# train_cont_R4.net
KiCad netlist of a schematic drawn in EAGLE
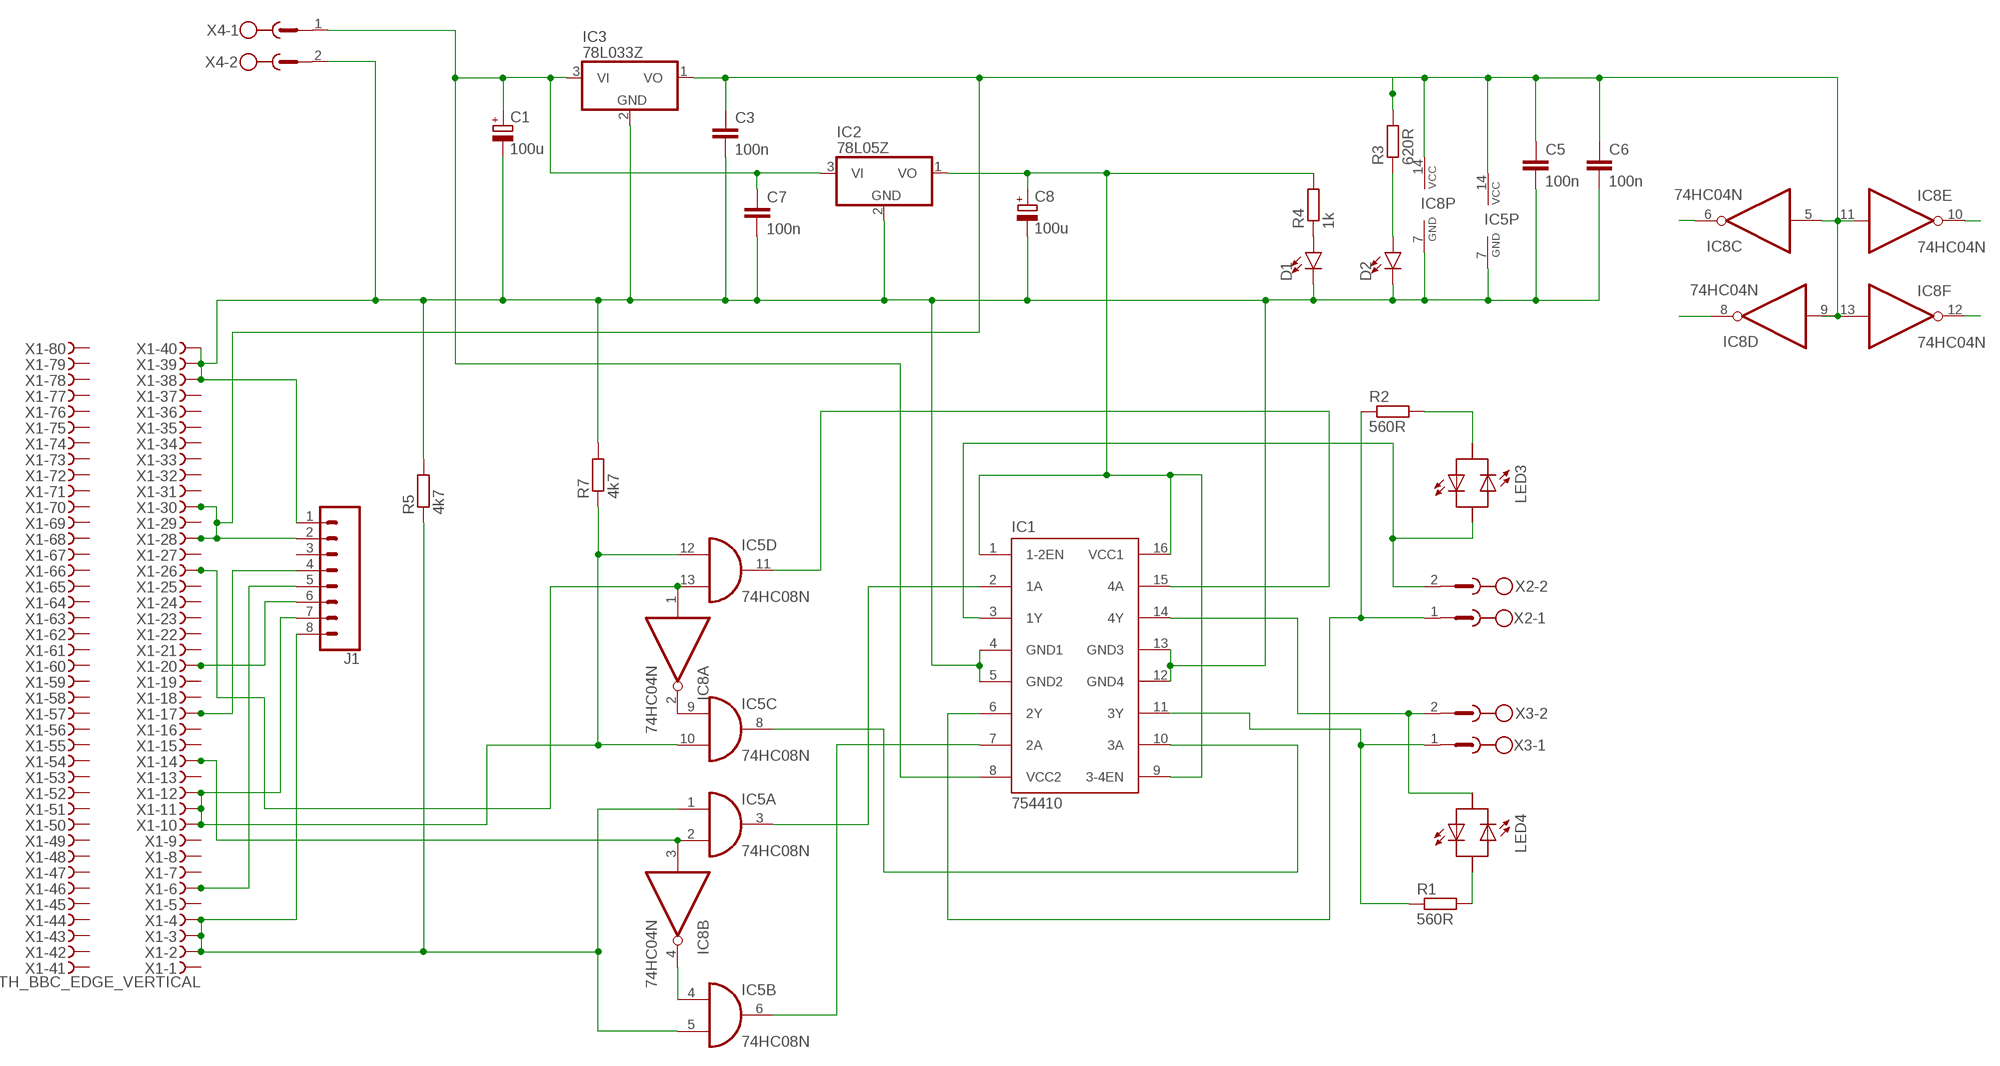
[diagram p0: schematic, sheet 1]

(export (version "E")
  (design (tool "Eeschema 10.0.6"))
  (components
    (comp (ref "C1")
      (value "100u")
      (footprint "eagle-import:E2,5-6E")
      (libsource (lib "eagle-import") (part "CPOL-EUE2,5-6E"))
    )
    (comp (ref "C3")
      (value "100n")
      (footprint "eagle-import:C050-025X075")
      (libsource (lib "eagle-import") (part "C-EU050-025X075"))
    )
    (comp (ref "C5")
      (value "100n")
      (footprint "eagle-import:C050-025X075")
      (libsource (lib "eagle-import") (part "C-EU050-025X075"))
    )
    (comp (ref "C6")
      (value "100n")
      (footprint "eagle-import:C050-025X075")
      (libsource (lib "eagle-import") (part "C-EU050-025X075"))
    )
    (comp (ref "C7")
      (value "100n")
      (footprint "eagle-import:C050-025X075")
      (libsource (lib "eagle-import") (part "C-EU050-025X075"))
    )
    (comp (ref "C8")
      (value "100u")
      (footprint "eagle-import:E2,5-6E")
      (libsource (lib "eagle-import") (part "CPOL-EUE2,5-6E"))
    )
    (comp (ref "D1")
      (value "LED3MM")
      (footprint "eagle-import:LED_3MM")
      (libsource (lib "eagle-import") (part "LED3MM"))
    )
    (comp (ref "D2")
      (value "LED3MM")
      (footprint "eagle-import:LED_3MM")
      (libsource (lib "eagle-import") (part "LED3MM"))
    )
    (comp (ref "IC1")
      (value "754410")
      (footprint "eagle-import:DIL16")
      (fields (field (name "MF") "Arrow Electronics") (field (name "MPN") "L293E"))
      (libsource (lib "eagle-import") (part "L293E"))
    )
    (comp (ref "IC2")
      (value "78L05Z")
      (footprint "eagle-import:TO92")
      (libsource (lib "eagle-import") (part "78ZL05"))
    )
    (comp (ref "IC3")
      (value "78L033Z")
      (footprint "eagle-import:TO92")
      (libsource (lib "eagle-import") (part "78ZL05"))
    )
    (comp (ref "IC5")
      (value "74HC08N")
      (footprint "eagle-import:DIL14")
      (libsource (lib "eagle-import") (part "7408NHC"))
    )
    (comp (ref "IC8")
      (value "74HC04N")
      (footprint "eagle-import:DIL14")
      (libsource (lib "eagle-import") (part "7404NAC"))
    )
    (comp (ref "J1")
      (value "CONN_08\"")
      (footprint "eagle-import:1X08")
      (libsource (lib "eagle-import") (part "CONN_08{dblquote}"))
    )
    (comp (ref "LED3")
      (value "LED_LED5MM")
      (footprint "eagle-import:LED_LED5MM")
      (libsource (lib "eagle-import") (part "LED_LED5MM"))
    )
    (comp (ref "LED4")
      (value "LED_LED5MM")
      (footprint "eagle-import:LED_LED5MM")
      (libsource (lib "eagle-import") (part "LED_LED5MM"))
    )
    (comp (ref "R1")
      (value "560R")
      (footprint "eagle-import:0207_10")
      (libsource (lib "eagle-import") (part "R-EU_0207/10"))
    )
    (comp (ref "R2")
      (value "560R")
      (footprint "eagle-import:0207_10")
      (libsource (lib "eagle-import") (part "R-EU_0207/10"))
    )
    (comp (ref "R3")
      (value "620R")
      (footprint "eagle-import:0207_10")
      (libsource (lib "eagle-import") (part "R-EU_0207/10"))
    )
    (comp (ref "R4")
      (value "1k")
      (footprint "eagle-import:0207_10")
      (libsource (lib "eagle-import") (part "R-EU_0207/10"))
    )
    (comp (ref "R5")
      (value "4k7")
      (footprint "eagle-import:0207_15")
      (libsource (lib "eagle-import") (part "R-EU_0207/15"))
    )
    (comp (ref "R7")
      (value "4k7")
      (footprint "eagle-import:0207_10")
      (libsource (lib "eagle-import") (part "R-EU_0207/10"))
    )
    (comp (ref "X1")
      (value "PTH_BBC_EDGE_VERTICAL")
      (footprint "eagle-import:PTH_BBC_EDGE")
      (libsource (lib "eagle-import") (part "PTH_BBC_EDGE_VERTICAL"))
    )
    (comp (ref "X2")
      (value "MSTBV2")
      (footprint "eagle-import:MSTBV2")
      (libsource (lib "eagle-import") (part "MSTBV2"))
    )
    (comp (ref "X3")
      (value "MSTBV2")
      (footprint "eagle-import:MSTBV2")
      (libsource (lib "eagle-import") (part "MSTBV2"))
    )
    (comp (ref "X4")
      (value "MSTBV2")
      (footprint "eagle-import:MSTBV2")
      (libsource (lib "eagle-import") (part "MSTBV2"))
    )
  )
  (nets
    (net (code "1") (name "Net-(D1-C)") (class "Default")
      (node (ref "C1") (pin "-") (pinfunction "-_-") (pintype "passive"))
      (node (ref "C3") (pin "2") (pinfunction "2_2") (pintype "passive"))
      (node (ref "C5") (pin "2") (pinfunction "2_2") (pintype "passive"))
      (node (ref "C6") (pin "2") (pinfunction "2_2") (pintype "passive"))
      (node (ref "C7") (pin "2") (pinfunction "2_2") (pintype "passive"))
      (node (ref "C8") (pin "-") (pinfunction "-_-") (pintype "passive"))
      (node (ref "D1") (pin "K") (pinfunction "C_K") (pintype "passive"))
      (node (ref "D2") (pin "K") (pinfunction "C_K") (pintype "passive"))
      (node (ref "IC1") (pin "12") (pinfunction "GND4_12") (pintype "power_in"))
      (node (ref "IC1") (pin "13") (pinfunction "GND3_13") (pintype "power_in"))
      (node (ref "IC1") (pin "4") (pinfunction "GND1_4") (pintype "power_in"))
      (node (ref "IC1") (pin "5") (pinfunction "GND2_5") (pintype "power_in"))
      (node (ref "IC2") (pin "2") (pinfunction "GND_2") (pintype "passive"))
      (node (ref "IC3") (pin "2") (pinfunction "GND_2") (pintype "passive"))
      (node (ref "IC5") (pin "7") (pinfunction "GND_7") (pintype "power_in"))
      (node (ref "IC8") (pin "7") (pinfunction "GND_7") (pintype "power_in"))
      (node (ref "J1") (pin "1") (pinfunction "1_1") (pintype "passive"))
      (node (ref "R5") (pin "2") (pinfunction "2_2") (pintype "passive"))
      (node (ref "R7") (pin "2") (pinfunction "2_2") (pintype "passive"))
      (node (ref "X1") (pin "38") (pinfunction "F_38") (pintype "passive"))
      (node (ref "X1") (pin "39") (pinfunction "F_39") (pintype "passive"))
      (node (ref "X1") (pin "40") (pinfunction "F_40") (pintype "passive"))
      (node (ref "X4") (pin "2") (pinfunction "SK_2") (pintype "passive"))
    )
    (net (code "2") (name "Net-(D1-PadA)") (class "Default")
      (node (ref "D1") (pin "A") (pinfunction "A_A") (pintype "passive"))
      (node (ref "R4") (pin "1") (pinfunction "1_1") (pintype "passive"))
    )
    (net (code "3") (name "Net-(D2-PadA)") (class "Default")
      (node (ref "D2") (pin "A") (pinfunction "A_A") (pintype "passive"))
      (node (ref "R3") (pin "1") (pinfunction "1_1") (pintype "passive"))
    )
    (net (code "4") (name "Net-(IC1-1-2EN)") (class "Default")
      (node (ref "C8") (pin "+") (pinfunction "+_+") (pintype "passive"))
      (node (ref "IC1") (pin "1") (pinfunction "1-2EN_1") (pintype "input"))
      (node (ref "IC1") (pin "16") (pinfunction "VCC1_16") (pintype "power_in"))
      (node (ref "IC1") (pin "9") (pinfunction "3-4EN_9") (pintype "input"))
      (node (ref "IC2") (pin "1") (pinfunction "VO_1") (pintype "passive"))
      (node (ref "R4") (pin "2") (pinfunction "2_2") (pintype "passive"))
    )
    (net (code "5") (name "Net-(IC1-1A)") (class "Default")
      (node (ref "IC1") (pin "2") (pinfunction "1A_2") (pintype "input"))
      (node (ref "IC5") (pin "3") (pinfunction "O_3") (pintype "output"))
    )
    (net (code "6") (name "Net-(IC1-1Y)") (class "Default")
      (node (ref "IC1") (pin "3") (pinfunction "1Y_3") (pintype "output"))
      (node (ref "LED3") (pin "K") (pinfunction "C_K") (pintype "passive"))
      (node (ref "X2") (pin "2") (pinfunction "SK_2") (pintype "passive"))
    )
    (net (code "7") (name "Net-(IC1-2A)") (class "Default")
      (node (ref "IC1") (pin "7") (pinfunction "2A_7") (pintype "input"))
      (node (ref "IC5") (pin "6") (pinfunction "O_6") (pintype "output"))
    )
    (net (code "8") (name "Net-(IC1-2Y)") (class "Default")
      (node (ref "IC1") (pin "6") (pinfunction "2Y_6") (pintype "output"))
      (node (ref "R2") (pin "1") (pinfunction "1_1") (pintype "passive"))
      (node (ref "X2") (pin "1") (pinfunction "SK_1") (pintype "passive"))
    )
    (net (code "9") (name "Net-(IC1-3A)") (class "Default")
      (node (ref "IC1") (pin "10") (pinfunction "3A_10") (pintype "input"))
      (node (ref "IC5") (pin "8") (pinfunction "O_8") (pintype "output"))
    )
    (net (code "10") (name "Net-(IC1-3Y)") (class "Default")
      (node (ref "IC1") (pin "11") (pinfunction "3Y_11") (pintype "output"))
      (node (ref "R1") (pin "1") (pinfunction "1_1") (pintype "passive"))
      (node (ref "X3") (pin "1") (pinfunction "SK_1") (pintype "passive"))
    )
    (net (code "11") (name "Net-(IC1-4A)") (class "Default")
      (node (ref "IC1") (pin "15") (pinfunction "4A_15") (pintype "input"))
      (node (ref "IC5") (pin "11") (pinfunction "O_11") (pintype "output"))
    )
    (net (code "12") (name "Net-(IC1-4Y)") (class "Default")
      (node (ref "IC1") (pin "14") (pinfunction "4Y_14") (pintype "output"))
      (node (ref "LED4") (pin "A") (pinfunction "A_A") (pintype "passive"))
      (node (ref "X3") (pin "2") (pinfunction "SK_2") (pintype "passive"))
    )
    (net (code "13") (name "Net-(IC1-VCC2)") (class "Default")
      (node (ref "C1") (pin "+") (pinfunction "+_+") (pintype "passive"))
      (node (ref "C7") (pin "1") (pinfunction "1_1") (pintype "passive"))
      (node (ref "IC1") (pin "8") (pinfunction "VCC2_8") (pintype "power_in"))
      (node (ref "IC2") (pin "3") (pinfunction "VI_3") (pintype "input"))
      (node (ref "IC3") (pin "3") (pinfunction "VI_3") (pintype "input"))
      (node (ref "X4") (pin "1") (pinfunction "SK_1") (pintype "passive"))
    )
    (net (code "14") (name "Net-(IC3-VO)") (class "Default")
      (node (ref "C3") (pin "1") (pinfunction "1_1") (pintype "passive"))
      (node (ref "C5") (pin "1") (pinfunction "1_1") (pintype "passive"))
      (node (ref "C6") (pin "1") (pinfunction "1_1") (pintype "passive"))
      (node (ref "IC3") (pin "1") (pinfunction "VO_1") (pintype "passive"))
      (node (ref "IC5") (pin "14") (pinfunction "VCC_14") (pintype "power_in"))
      (node (ref "IC8") (pin "11") (pinfunction "I_11") (pintype "input"))
      (node (ref "IC8") (pin "13") (pinfunction "I_13") (pintype "input"))
      (node (ref "IC8") (pin "14") (pinfunction "VCC_14") (pintype "power_in"))
      (node (ref "IC8") (pin "5") (pinfunction "I_5") (pintype "input"))
      (node (ref "IC8") (pin "9") (pinfunction "I_9") (pintype "input"))
      (node (ref "J1") (pin "2") (pinfunction "2_2") (pintype "passive"))
      (node (ref "R3") (pin "2") (pinfunction "2_2") (pintype "passive"))
      (node (ref "X1") (pin "28") (pinfunction "F_28") (pintype "passive"))
      (node (ref "X1") (pin "30") (pinfunction "F_30") (pintype "passive"))
    )
    (net (code "15") (name "Net-(IC5A-I0)") (class "Default")
      (node (ref "IC5") (pin "1") (pinfunction "I0_1") (pintype "input"))
      (node (ref "IC5") (pin "5") (pinfunction "I1_5") (pintype "input"))
      (node (ref "J1") (pin "8") (pinfunction "8_8") (pintype "passive"))
      (node (ref "R5") (pin "1") (pinfunction "1_1") (pintype "passive"))
      (node (ref "X1") (pin "2") (pinfunction "F_2") (pintype "passive"))
      (node (ref "X1") (pin "3") (pinfunction "F_3") (pintype "passive"))
      (node (ref "X1") (pin "4") (pinfunction "F_4") (pintype "passive"))
    )
    (net (code "16") (name "Net-(IC5A-I1)") (class "Default")
      (node (ref "IC5") (pin "2") (pinfunction "I1_2") (pintype "input"))
      (node (ref "IC8") (pin "3") (pinfunction "I_3") (pintype "input"))
      (node (ref "X1") (pin "14") (pinfunction "F_14") (pintype "passive"))
    )
    (net (code "17") (name "Net-(IC5B-I0)") (class "Default")
      (node (ref "IC5") (pin "4") (pinfunction "I0_4") (pintype "input"))
      (node (ref "IC8") (pin "4") (pinfunction "O_4") (pintype "output"))
    )
    (net (code "18") (name "Net-(IC5C-I0)") (class "Default")
      (node (ref "IC5") (pin "9") (pinfunction "I0_9") (pintype "input"))
      (node (ref "IC8") (pin "2") (pinfunction "O_2") (pintype "output"))
    )
    (net (code "19") (name "Net-(IC5C-I1)") (class "Default")
      (node (ref "IC5") (pin "10") (pinfunction "I1_10") (pintype "input"))
      (node (ref "IC5") (pin "12") (pinfunction "I0_12") (pintype "input"))
      (node (ref "J1") (pin "7") (pinfunction "7_7") (pintype "passive"))
      (node (ref "R7") (pin "1") (pinfunction "1_1") (pintype "passive"))
      (node (ref "X1") (pin "10") (pinfunction "F_10") (pintype "passive"))
      (node (ref "X1") (pin "11") (pinfunction "F_11") (pintype "passive"))
      (node (ref "X1") (pin "12") (pinfunction "F_12") (pintype "passive"))
    )
    (net (code "20") (name "Net-(IC5D-I1)") (class "Default")
      (node (ref "IC5") (pin "13") (pinfunction "I1_13") (pintype "input"))
      (node (ref "IC8") (pin "1") (pinfunction "I_1") (pintype "input"))
      (node (ref "X1") (pin "26") (pinfunction "F_26") (pintype "passive"))
    )
    (net (code "21") (name "Net-(LED3-PadA)") (class "Default")
      (node (ref "LED3") (pin "A") (pinfunction "A_A") (pintype "passive"))
      (node (ref "R2") (pin "2") (pinfunction "2_2") (pintype "passive"))
    )
    (net (code "22") (name "Net-(LED4-C)") (class "Default")
      (node (ref "LED4") (pin "K") (pinfunction "C_K") (pintype "passive"))
      (node (ref "R1") (pin "2") (pinfunction "2_2") (pintype "passive"))
    )
    (net (code "23") (name "Net-(X1BD-F)") (class "Default")
      (node (ref "J1") (pin "5") (pinfunction "5_5") (pintype "passive"))
      (node (ref "X1") (pin "6") (pinfunction "F_6") (pintype "passive"))
    )
    (net (code "24") (name "Net-(X1I-F)") (class "Default")
      (node (ref "J1") (pin "4") (pinfunction "4_4") (pintype "passive"))
      (node (ref "X1") (pin "17") (pinfunction "F_17") (pintype "passive"))
    )
    (net (code "25") (name "Net-(X1M-F)") (class "Default")
      (node (ref "J1") (pin "6") (pinfunction "6_6") (pintype "passive"))
      (node (ref "X1") (pin "20") (pinfunction "F_20") (pintype "passive"))
    )
    (net (code "26") (name "unconnected-(IC8C-O-Pad6)") (class "Default")
      (node (ref "IC8") (pin "6") (pinfunction "O_6") (pintype "output"))
    )
    (net (code "27") (name "unconnected-(IC8D-O-Pad8)") (class "Default")
      (node (ref "IC8") (pin "8") (pinfunction "O_8") (pintype "output"))
    )
    (net (code "28") (name "unconnected-(IC8E-O-Pad10)") (class "Default")
      (node (ref "IC8") (pin "10") (pinfunction "O_10") (pintype "output"))
    )
    (net (code "29") (name "unconnected-(IC8F-O-Pad12)") (class "Default")
      (node (ref "IC8") (pin "12") (pinfunction "O_12") (pintype "output"))
    )
    (net (code "30") (name "unconnected-(J1-Pad3)") (class "Default")
      (node (ref "J1") (pin "3") (pinfunction "3_3") (pintype "passive"))
    )
    (net (code "31") (name "unconnected-(X1A-F-Pad1)") (class "Default")
      (node (ref "X1") (pin "1") (pinfunction "F_1") (pintype "passive"))
    )
    (net (code "32") (name "unconnected-(X1AA-F-Pad33)") (class "Default")
      (node (ref "X1") (pin "33") (pinfunction "F_33") (pintype "passive"))
    )
    (net (code "33") (name "unconnected-(X1AB-F-Pad34)") (class "Default")
      (node (ref "X1") (pin "34") (pinfunction "F_34") (pintype "passive"))
    )
    (net (code "34") (name "unconnected-(X1AC-F-Pad35)") (class "Default")
      (node (ref "X1") (pin "35") (pinfunction "F_35") (pintype "passive"))
    )
    (net (code "35") (name "unconnected-(X1AD-F-Pad36)") (class "Default")
      (node (ref "X1") (pin "36") (pinfunction "F_36") (pintype "passive"))
    )
    (net (code "36") (name "unconnected-(X1AE-F-Pad37)") (class "Default")
      (node (ref "X1") (pin "37") (pinfunction "F_37") (pintype "passive"))
    )
    (net (code "37") (name "unconnected-(X1AJ-F-Pad41)") (class "Default")
      (node (ref "X1") (pin "41") (pinfunction "F_41") (pintype "passive"))
    )
    (net (code "38") (name "unconnected-(X1AK-F-Pad42)") (class "Default")
      (node (ref "X1") (pin "42") (pinfunction "F_42") (pintype "passive"))
    )
    (net (code "39") (name "unconnected-(X1AL-F-Pad43)") (class "Default")
      (node (ref "X1") (pin "43") (pinfunction "F_43") (pintype "passive"))
    )
    (net (code "40") (name "unconnected-(X1AM-F-Pad44)") (class "Default")
      (node (ref "X1") (pin "44") (pinfunction "F_44") (pintype "passive"))
    )
    (net (code "41") (name "unconnected-(X1AN-F-Pad45)") (class "Default")
      (node (ref "X1") (pin "45") (pinfunction "F_45") (pintype "passive"))
    )
    (net (code "42") (name "unconnected-(X1AO-F-Pad46)") (class "Default")
      (node (ref "X1") (pin "46") (pinfunction "F_46") (pintype "passive"))
    )
    (net (code "43") (name "unconnected-(X1AP-F-Pad47)") (class "Default")
      (node (ref "X1") (pin "47") (pinfunction "F_47") (pintype "passive"))
    )
    (net (code "44") (name "unconnected-(X1AQ-F-Pad48)") (class "Default")
      (node (ref "X1") (pin "48") (pinfunction "F_48") (pintype "passive"))
    )
    (net (code "45") (name "unconnected-(X1AR-F-Pad49)") (class "Default")
      (node (ref "X1") (pin "49") (pinfunction "F_49") (pintype "passive"))
    )
    (net (code "46") (name "unconnected-(X1AS-F-Pad5)") (class "Default")
      (node (ref "X1") (pin "5") (pinfunction "F_5") (pintype "passive"))
    )
    (net (code "47") (name "unconnected-(X1AT-F-Pad50)") (class "Default")
      (node (ref "X1") (pin "50") (pinfunction "F_50") (pintype "passive"))
    )
    (net (code "48") (name "unconnected-(X1AU-F-Pad51)") (class "Default")
      (node (ref "X1") (pin "51") (pinfunction "F_51") (pintype "passive"))
    )
    (net (code "49") (name "unconnected-(X1AV-F-Pad52)") (class "Default")
      (node (ref "X1") (pin "52") (pinfunction "F_52") (pintype "passive"))
    )
    (net (code "50") (name "unconnected-(X1AW-F-Pad53)") (class "Default")
      (node (ref "X1") (pin "53") (pinfunction "F_53") (pintype "passive"))
    )
    (net (code "51") (name "unconnected-(X1AX-F-Pad54)") (class "Default")
      (node (ref "X1") (pin "54") (pinfunction "F_54") (pintype "passive"))
    )
    (net (code "52") (name "unconnected-(X1AY-F-Pad55)") (class "Default")
      (node (ref "X1") (pin "55") (pinfunction "F_55") (pintype "passive"))
    )
    (net (code "53") (name "unconnected-(X1AZ-F-Pad56)") (class "Default")
      (node (ref "X1") (pin "56") (pinfunction "F_56") (pintype "passive"))
    )
    (net (code "54") (name "unconnected-(X1BA-F-Pad57)") (class "Default")
      (node (ref "X1") (pin "57") (pinfunction "F_57") (pintype "passive"))
    )
    (net (code "55") (name "unconnected-(X1BB-F-Pad58)") (class "Default")
      (node (ref "X1") (pin "58") (pinfunction "F_58") (pintype "passive"))
    )
    (net (code "56") (name "unconnected-(X1BC-F-Pad59)") (class "Default")
      (node (ref "X1") (pin "59") (pinfunction "F_59") (pintype "passive"))
    )
    (net (code "57") (name "unconnected-(X1BE-F-Pad60)") (class "Default")
      (node (ref "X1") (pin "60") (pinfunction "F_60") (pintype "passive"))
    )
    (net (code "58") (name "unconnected-(X1BF-F-Pad61)") (class "Default")
      (node (ref "X1") (pin "61") (pinfunction "F_61") (pintype "passive"))
    )
    (net (code "59") (name "unconnected-(X1BG-F-Pad62)") (class "Default")
      (node (ref "X1") (pin "62") (pinfunction "F_62") (pintype "passive"))
    )
    (net (code "60") (name "unconnected-(X1BH-F-Pad63)") (class "Default")
      (node (ref "X1") (pin "63") (pinfunction "F_63") (pintype "passive"))
    )
    (net (code "61") (name "unconnected-(X1BI-F-Pad64)") (class "Default")
      (node (ref "X1") (pin "64") (pinfunction "F_64") (pintype "passive"))
    )
    (net (code "62") (name "unconnected-(X1BJ-F-Pad65)") (class "Default")
      (node (ref "X1") (pin "65") (pinfunction "F_65") (pintype "passive"))
    )
    (net (code "63") (name "unconnected-(X1BK-F-Pad66)") (class "Default")
      (node (ref "X1") (pin "66") (pinfunction "F_66") (pintype "passive"))
    )
    (net (code "64") (name "unconnected-(X1BL-F-Pad67)") (class "Default")
      (node (ref "X1") (pin "67") (pinfunction "F_67") (pintype "passive"))
    )
    (net (code "65") (name "unconnected-(X1BM-F-Pad68)") (class "Default")
      (node (ref "X1") (pin "68") (pinfunction "F_68") (pintype "passive"))
    )
    (net (code "66") (name "unconnected-(X1BN-F-Pad69)") (class "Default")
      (node (ref "X1") (pin "69") (pinfunction "F_69") (pintype "passive"))
    )
    (net (code "67") (name "unconnected-(X1BO-F-Pad7)") (class "Default")
      (node (ref "X1") (pin "7") (pinfunction "F_7") (pintype "passive"))
    )
    (net (code "68") (name "unconnected-(X1BP-F-Pad70)") (class "Default")
      (node (ref "X1") (pin "70") (pinfunction "F_70") (pintype "passive"))
    )
    (net (code "69") (name "unconnected-(X1BQ-F-Pad71)") (class "Default")
      (node (ref "X1") (pin "71") (pinfunction "F_71") (pintype "passive"))
    )
    (net (code "70") (name "unconnected-(X1BR-F-Pad72)") (class "Default")
      (node (ref "X1") (pin "72") (pinfunction "F_72") (pintype "passive"))
    )
    (net (code "71") (name "unconnected-(X1BS-F-Pad73)") (class "Default")
      (node (ref "X1") (pin "73") (pinfunction "F_73") (pintype "passive"))
    )
    (net (code "72") (name "unconnected-(X1BT-F-Pad74)") (class "Default")
      (node (ref "X1") (pin "74") (pinfunction "F_74") (pintype "passive"))
    )
    (net (code "73") (name "unconnected-(X1BU-F-Pad75)") (class "Default")
      (node (ref "X1") (pin "75") (pinfunction "F_75") (pintype "passive"))
    )
    (net (code "74") (name "unconnected-(X1BV-F-Pad76)") (class "Default")
      (node (ref "X1") (pin "76") (pinfunction "F_76") (pintype "passive"))
    )
    (net (code "75") (name "unconnected-(X1BW-F-Pad77)") (class "Default")
      (node (ref "X1") (pin "77") (pinfunction "F_77") (pintype "passive"))
    )
    (net (code "76") (name "unconnected-(X1BX-F-Pad78)") (class "Default")
      (node (ref "X1") (pin "78") (pinfunction "F_78") (pintype "passive"))
    )
    (net (code "77") (name "unconnected-(X1BY-F-Pad79)") (class "Default")
      (node (ref "X1") (pin "79") (pinfunction "F_79") (pintype "passive"))
    )
    (net (code "78") (name "unconnected-(X1BZ-F-Pad8)") (class "Default")
      (node (ref "X1") (pin "8") (pinfunction "F_8") (pintype "passive"))
    )
    (net (code "79") (name "unconnected-(X1CA-F-Pad80)") (class "Default")
      (node (ref "X1") (pin "80") (pinfunction "F_80") (pintype "passive"))
    )
    (net (code "80") (name "unconnected-(X1CB-F-Pad9)") (class "Default")
      (node (ref "X1") (pin "9") (pinfunction "F_9") (pintype "passive"))
    )
    (net (code "81") (name "unconnected-(X1E-F-Pad13)") (class "Default")
      (node (ref "X1") (pin "13") (pinfunction "F_13") (pintype "passive"))
    )
    (net (code "82") (name "unconnected-(X1G-F-Pad15)") (class "Default")
      (node (ref "X1") (pin "15") (pinfunction "F_15") (pintype "passive"))
    )
    (net (code "83") (name "unconnected-(X1H-F-Pad16)") (class "Default")
      (node (ref "X1") (pin "16") (pinfunction "F_16") (pintype "passive"))
    )
    (net (code "84") (name "unconnected-(X1J-F-Pad18)") (class "Default")
      (node (ref "X1") (pin "18") (pinfunction "F_18") (pintype "passive"))
    )
    (net (code "85") (name "unconnected-(X1K-F-Pad19)") (class "Default")
      (node (ref "X1") (pin "19") (pinfunction "F_19") (pintype "passive"))
    )
    (net (code "86") (name "unconnected-(X1N-F-Pad21)") (class "Default")
      (node (ref "X1") (pin "21") (pinfunction "F_21") (pintype "passive"))
    )
    (net (code "87") (name "unconnected-(X1O-F-Pad22)") (class "Default")
      (node (ref "X1") (pin "22") (pinfunction "F_22") (pintype "passive"))
    )
    (net (code "88") (name "unconnected-(X1P-F-Pad23)") (class "Default")
      (node (ref "X1") (pin "23") (pinfunction "F_23") (pintype "passive"))
    )
    (net (code "89") (name "unconnected-(X1Q-F-Pad24)") (class "Default")
      (node (ref "X1") (pin "24") (pinfunction "F_24") (pintype "passive"))
    )
    (net (code "90") (name "unconnected-(X1R-F-Pad25)") (class "Default")
      (node (ref "X1") (pin "25") (pinfunction "F_25") (pintype "passive"))
    )
    (net (code "91") (name "unconnected-(X1T-F-Pad27)") (class "Default")
      (node (ref "X1") (pin "27") (pinfunction "F_27") (pintype "passive"))
    )
    (net (code "92") (name "unconnected-(X1V-F-Pad29)") (class "Default")
      (node (ref "X1") (pin "29") (pinfunction "F_29") (pintype "passive"))
    )
    (net (code "93") (name "unconnected-(X1Y-F-Pad31)") (class "Default")
      (node (ref "X1") (pin "31") (pinfunction "F_31") (pintype "passive"))
    )
    (net (code "94") (name "unconnected-(X1Z-F-Pad32)") (class "Default")
      (node (ref "X1") (pin "32") (pinfunction "F_32") (pintype "passive"))
    )
  )
)
